# Connector.net
KiCad netlist of a schematic drawn in Altium Designer
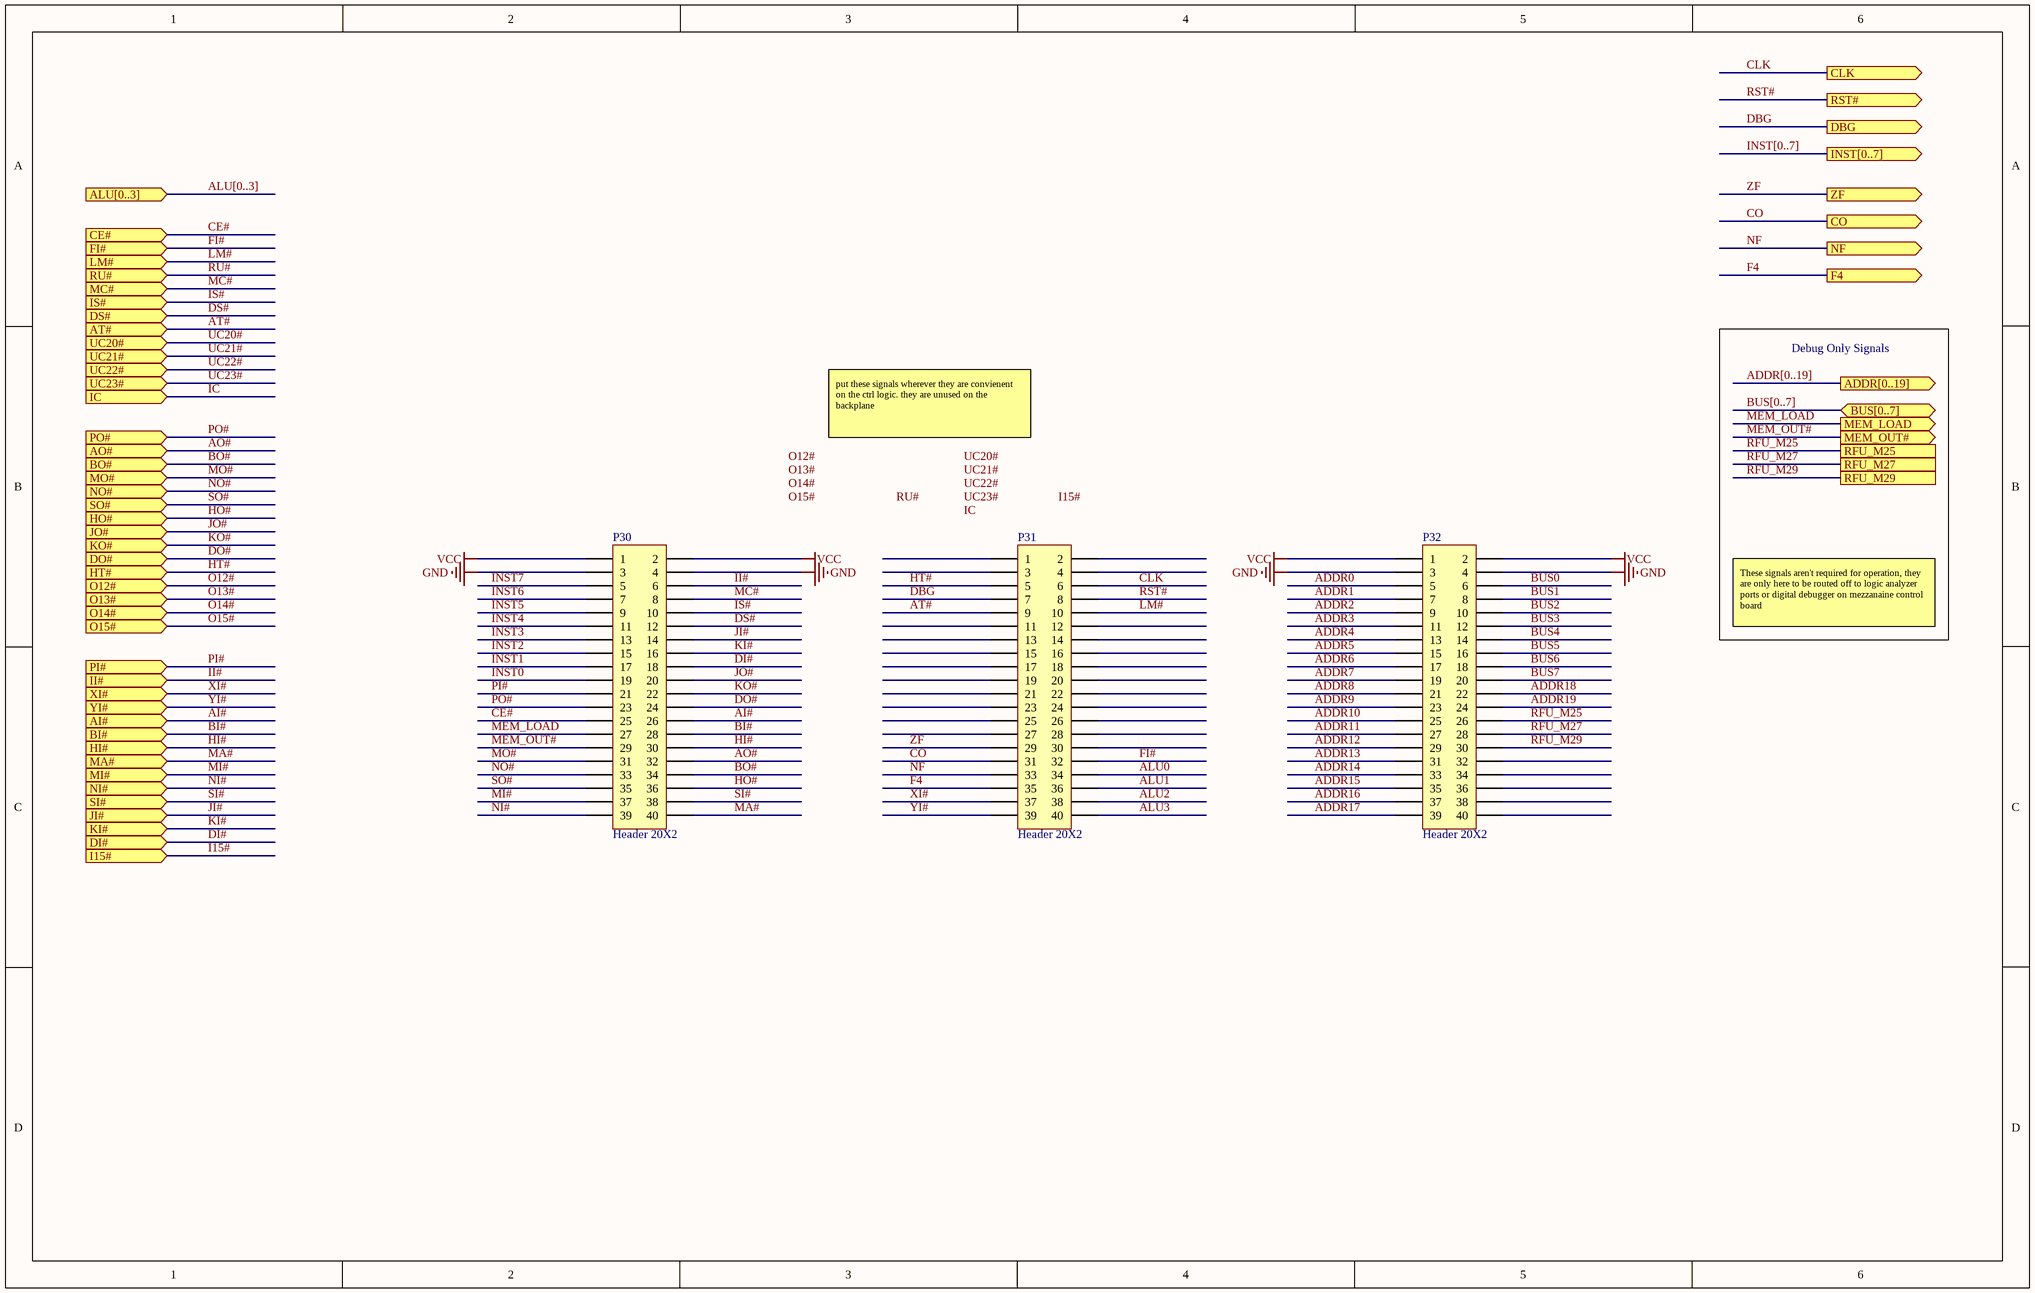
[diagram p0: Connector.SchDoc]

(export (version "E")
  (design (tool "Eeschema 10.0.6"))
  (components
    (comp (ref "P30")
      (value "Header 20X2")
      (footprint "HDR2X20")
      (description "Header, 20-Pin, Dual row")
      (fields (field (name "PUBLISHER") "Altium Limited"))
      (libsource (lib "Miscellaneous Connectors") (part "Header 20X2"))
    )
    (comp (ref "P31")
      (value "Header 20X2")
      (footprint "HDR2X20")
      (description "Header, 20-Pin, Dual row")
      (fields (field (name "PUBLISHER") "Altium Limited"))
      (libsource (lib "Miscellaneous Connectors") (part "Header 20X2"))
    )
    (comp (ref "P32")
      (value "Header 20X2")
      (footprint "HDR2X20")
      (description "Header, 20-Pin, Dual row")
      (fields (field (name "PUBLISHER") "Altium Limited"))
      (libsource (lib "Miscellaneous Connectors") (part "Header 20X2"))
    )
  )
  (nets
    (net (code "1") (name "/ADDR0") (class "Default")
      (node (ref "P32") (pin "5") (pinfunction "5_5") (pintype "passive"))
    )
    (net (code "2") (name "/ADDR1") (class "Default")
      (node (ref "P32") (pin "7") (pinfunction "7_7") (pintype "passive"))
    )
    (net (code "3") (name "/ADDR2") (class "Default")
      (node (ref "P32") (pin "9") (pinfunction "9_9") (pintype "passive"))
    )
    (net (code "4") (name "/ADDR3") (class "Default")
      (node (ref "P32") (pin "11") (pinfunction "11_11") (pintype "passive"))
    )
    (net (code "5") (name "/ADDR4") (class "Default")
      (node (ref "P32") (pin "13") (pinfunction "13_13") (pintype "passive"))
    )
    (net (code "6") (name "/ADDR5") (class "Default")
      (node (ref "P32") (pin "15") (pinfunction "15_15") (pintype "passive"))
    )
    (net (code "7") (name "/ADDR6") (class "Default")
      (node (ref "P32") (pin "17") (pinfunction "17_17") (pintype "passive"))
    )
    (net (code "8") (name "/ADDR7") (class "Default")
      (node (ref "P32") (pin "19") (pinfunction "19_19") (pintype "passive"))
    )
    (net (code "9") (name "/ADDR8") (class "Default")
      (node (ref "P32") (pin "21") (pinfunction "21_21") (pintype "passive"))
    )
    (net (code "10") (name "/ADDR9") (class "Default")
      (node (ref "P32") (pin "23") (pinfunction "23_23") (pintype "passive"))
    )
    (net (code "11") (name "/ADDR10") (class "Default")
      (node (ref "P32") (pin "25") (pinfunction "25_25") (pintype "passive"))
    )
    (net (code "12") (name "/ADDR11") (class "Default")
      (node (ref "P32") (pin "27") (pinfunction "27_27") (pintype "passive"))
    )
    (net (code "13") (name "/ADDR12") (class "Default")
      (node (ref "P32") (pin "29") (pinfunction "29_29") (pintype "passive"))
    )
    (net (code "14") (name "/ADDR13") (class "Default")
      (node (ref "P32") (pin "31") (pinfunction "31_31") (pintype "passive"))
    )
    (net (code "15") (name "/ADDR14") (class "Default")
      (node (ref "P32") (pin "33") (pinfunction "33_33") (pintype "passive"))
    )
    (net (code "16") (name "/ADDR15") (class "Default")
      (node (ref "P32") (pin "35") (pinfunction "35_35") (pintype "passive"))
    )
    (net (code "17") (name "/ADDR16") (class "Default")
      (node (ref "P32") (pin "37") (pinfunction "37_37") (pintype "passive"))
    )
    (net (code "18") (name "/ADDR17") (class "Default")
      (node (ref "P32") (pin "39") (pinfunction "39_39") (pintype "passive"))
    )
    (net (code "19") (name "/ADDR18") (class "Default")
      (node (ref "P32") (pin "22") (pinfunction "22_22") (pintype "passive"))
    )
    (net (code "20") (name "/ADDR19") (class "Default")
      (node (ref "P32") (pin "24") (pinfunction "24_24") (pintype "passive"))
    )
    (net (code "22") (name "/AI#") (class "Default")
      (node (ref "P30") (pin "26") (pinfunction "26_26") (pintype "passive"))
    )
    (net (code "23") (name "/ALU0") (class "Default")
      (node (ref "P31") (pin "34") (pinfunction "34_34") (pintype "passive"))
    )
    (net (code "24") (name "/ALU1") (class "Default")
      (node (ref "P31") (pin "36") (pinfunction "36_36") (pintype "passive"))
    )
    (net (code "25") (name "/ALU2") (class "Default")
      (node (ref "P31") (pin "38") (pinfunction "38_38") (pintype "passive"))
    )
    (net (code "26") (name "/ALU3") (class "Default")
      (node (ref "P31") (pin "40") (pinfunction "40_40") (pintype "passive"))
    )
    (net (code "28") (name "/AO#") (class "Default")
      (node (ref "P30") (pin "32") (pinfunction "32_32") (pintype "passive"))
    )
    (net (code "29") (name "/AT#") (class "Default")
      (node (ref "P31") (pin "9") (pinfunction "9_9") (pintype "passive"))
    )
    (net (code "30") (name "/BI#") (class "Default")
      (node (ref "P30") (pin "28") (pinfunction "28_28") (pintype "passive"))
    )
    (net (code "31") (name "/BO#") (class "Default")
      (node (ref "P30") (pin "34") (pinfunction "34_34") (pintype "passive"))
    )
    (net (code "32") (name "/BUS0") (class "Default")
      (node (ref "P32") (pin "6") (pinfunction "6_6") (pintype "passive"))
    )
    (net (code "33") (name "/BUS1") (class "Default")
      (node (ref "P32") (pin "8") (pinfunction "8_8") (pintype "passive"))
    )
    (net (code "34") (name "/BUS2") (class "Default")
      (node (ref "P32") (pin "10") (pinfunction "10_10") (pintype "passive"))
    )
    (net (code "35") (name "/BUS3") (class "Default")
      (node (ref "P32") (pin "12") (pinfunction "12_12") (pintype "passive"))
    )
    (net (code "36") (name "/BUS4") (class "Default")
      (node (ref "P32") (pin "14") (pinfunction "14_14") (pintype "passive"))
    )
    (net (code "37") (name "/BUS5") (class "Default")
      (node (ref "P32") (pin "16") (pinfunction "16_16") (pintype "passive"))
    )
    (net (code "38") (name "/BUS6") (class "Default")
      (node (ref "P32") (pin "18") (pinfunction "18_18") (pintype "passive"))
    )
    (net (code "39") (name "/BUS7") (class "Default")
      (node (ref "P32") (pin "20") (pinfunction "20_20") (pintype "passive"))
    )
    (net (code "41") (name "/CE#") (class "Default")
      (node (ref "P30") (pin "25") (pinfunction "25_25") (pintype "passive"))
    )
    (net (code "42") (name "/CLK") (class "Default")
      (node (ref "P31") (pin "6") (pinfunction "6_6") (pintype "passive"))
    )
    (net (code "43") (name "/CO") (class "Default")
      (node (ref "P31") (pin "31") (pinfunction "31_31") (pintype "passive"))
    )
    (net (code "44") (name "/DBG") (class "Default")
      (node (ref "P31") (pin "7") (pinfunction "7_7") (pintype "passive"))
    )
    (net (code "45") (name "/DI#") (class "Default")
      (node (ref "P30") (pin "18") (pinfunction "18_18") (pintype "passive"))
    )
    (net (code "46") (name "/DO#") (class "Default")
      (node (ref "P30") (pin "24") (pinfunction "24_24") (pintype "passive"))
    )
    (net (code "47") (name "/DS#") (class "Default")
      (node (ref "P30") (pin "12") (pinfunction "12_12") (pintype "passive"))
    )
    (net (code "48") (name "/F4") (class "Default")
      (node (ref "P31") (pin "35") (pinfunction "35_35") (pintype "passive"))
    )
    (net (code "49") (name "/FI#") (class "Default")
      (node (ref "P31") (pin "32") (pinfunction "32_32") (pintype "passive"))
    )
    (net (code "50") (name "/HI#") (class "Default")
      (node (ref "P30") (pin "30") (pinfunction "30_30") (pintype "passive"))
    )
    (net (code "51") (name "/HO#") (class "Default")
      (node (ref "P30") (pin "36") (pinfunction "36_36") (pintype "passive"))
    )
    (net (code "52") (name "/HT#") (class "Default")
      (node (ref "P31") (pin "5") (pinfunction "5_5") (pintype "passive"))
    )
    (net (code "55") (name "/II#") (class "Default")
      (node (ref "P30") (pin "6") (pinfunction "6_6") (pintype "passive"))
    )
    (net (code "56") (name "/INST0") (class "Default")
      (node (ref "P30") (pin "19") (pinfunction "19_19") (pintype "passive"))
    )
    (net (code "57") (name "/INST1") (class "Default")
      (node (ref "P30") (pin "17") (pinfunction "17_17") (pintype "passive"))
    )
    (net (code "58") (name "/INST2") (class "Default")
      (node (ref "P30") (pin "15") (pinfunction "15_15") (pintype "passive"))
    )
    (net (code "59") (name "/INST3") (class "Default")
      (node (ref "P30") (pin "13") (pinfunction "13_13") (pintype "passive"))
    )
    (net (code "60") (name "/INST4") (class "Default")
      (node (ref "P30") (pin "11") (pinfunction "11_11") (pintype "passive"))
    )
    (net (code "61") (name "/INST5") (class "Default")
      (node (ref "P30") (pin "9") (pinfunction "9_9") (pintype "passive"))
    )
    (net (code "62") (name "/INST6") (class "Default")
      (node (ref "P30") (pin "7") (pinfunction "7_7") (pintype "passive"))
    )
    (net (code "63") (name "/INST7") (class "Default")
      (node (ref "P30") (pin "5") (pinfunction "5_5") (pintype "passive"))
    )
    (net (code "65") (name "/IS#") (class "Default")
      (node (ref "P30") (pin "10") (pinfunction "10_10") (pintype "passive"))
    )
    (net (code "66") (name "/JI#") (class "Default")
      (node (ref "P30") (pin "14") (pinfunction "14_14") (pintype "passive"))
    )
    (net (code "67") (name "/JO#") (class "Default")
      (node (ref "P30") (pin "20") (pinfunction "20_20") (pintype "passive"))
    )
    (net (code "68") (name "/KI#") (class "Default")
      (node (ref "P30") (pin "16") (pinfunction "16_16") (pintype "passive"))
    )
    (net (code "69") (name "/KO#") (class "Default")
      (node (ref "P30") (pin "22") (pinfunction "22_22") (pintype "passive"))
    )
    (net (code "70") (name "/LM#") (class "Default")
      (node (ref "P31") (pin "10") (pinfunction "10_10") (pintype "passive"))
    )
    (net (code "71") (name "/MA#") (class "Default")
      (node (ref "P30") (pin "40") (pinfunction "40_40") (pintype "passive"))
    )
    (net (code "72") (name "/MC#") (class "Default")
      (node (ref "P30") (pin "8") (pinfunction "8_8") (pintype "passive"))
    )
    (net (code "73") (name "/MEM_LOAD") (class "Default")
      (node (ref "P30") (pin "27") (pinfunction "27_27") (pintype "passive"))
    )
    (net (code "74") (name "/MEM_OUT#") (class "Default")
      (node (ref "P30") (pin "29") (pinfunction "29_29") (pintype "passive"))
    )
    (net (code "75") (name "/MI#") (class "Default")
      (node (ref "P30") (pin "37") (pinfunction "37_37") (pintype "passive"))
    )
    (net (code "76") (name "/MO#") (class "Default")
      (node (ref "P30") (pin "31") (pinfunction "31_31") (pintype "passive"))
    )
    (net (code "77") (name "/NF") (class "Default")
      (node (ref "P31") (pin "33") (pinfunction "33_33") (pintype "passive"))
    )
    (net (code "78") (name "/NI#") (class "Default")
      (node (ref "P30") (pin "39") (pinfunction "39_39") (pintype "passive"))
    )
    (net (code "79") (name "/NO#") (class "Default")
      (node (ref "P30") (pin "33") (pinfunction "33_33") (pintype "passive"))
    )
    (net (code "84") (name "/PI#") (class "Default")
      (node (ref "P30") (pin "21") (pinfunction "21_21") (pintype "passive"))
    )
    (net (code "85") (name "/PO#") (class "Default")
      (node (ref "P30") (pin "23") (pinfunction "23_23") (pintype "passive"))
    )
    (net (code "86") (name "/RFU_M25") (class "Default")
      (node (ref "P32") (pin "26") (pinfunction "26_26") (pintype "passive"))
    )
    (net (code "87") (name "/RFU_M27") (class "Default")
      (node (ref "P32") (pin "28") (pinfunction "28_28") (pintype "passive"))
    )
    (net (code "88") (name "/RFU_M29") (class "Default")
      (node (ref "P32") (pin "30") (pinfunction "30_30") (pintype "passive"))
    )
    (net (code "89") (name "/RST#") (class "Default")
      (node (ref "P31") (pin "8") (pinfunction "8_8") (pintype "passive"))
    )
    (net (code "91") (name "/SI#") (class "Default")
      (node (ref "P30") (pin "38") (pinfunction "38_38") (pintype "passive"))
    )
    (net (code "92") (name "/SO#") (class "Default")
      (node (ref "P30") (pin "35") (pinfunction "35_35") (pintype "passive"))
    )
    (net (code "97") (name "/XI#") (class "Default")
      (node (ref "P31") (pin "37") (pinfunction "37_37") (pintype "passive"))
    )
    (net (code "98") (name "/YI#") (class "Default")
      (node (ref "P31") (pin "39") (pinfunction "39_39") (pintype "passive"))
    )
    (net (code "99") (name "/ZF") (class "Default")
      (node (ref "P31") (pin "29") (pinfunction "29_29") (pintype "passive"))
    )
    (net (code "100") (name "GND") (class "Default")
      (node (ref "P30") (pin "3") (pinfunction "3_3") (pintype "passive"))
      (node (ref "P30") (pin "4") (pinfunction "4_4") (pintype "passive"))
      (node (ref "P32") (pin "3") (pinfunction "3_3") (pintype "passive"))
      (node (ref "P32") (pin "4") (pinfunction "4_4") (pintype "passive"))
    )
    (net (code "101") (name "VCC") (class "Default")
      (node (ref "P30") (pin "1") (pinfunction "1_1") (pintype "passive"))
      (node (ref "P30") (pin "2") (pinfunction "2_2") (pintype "passive"))
      (node (ref "P32") (pin "1") (pinfunction "1_1") (pintype "passive"))
      (node (ref "P32") (pin "2") (pinfunction "2_2") (pintype "passive"))
    )
    (net (code "102") (name "unconnected-(P31-Pad1)") (class "Default")
      (node (ref "P31") (pin "1") (pinfunction "1_1") (pintype "passive"))
    )
    (net (code "103") (name "unconnected-(P31-Pad2)") (class "Default")
      (node (ref "P31") (pin "2") (pinfunction "2_2") (pintype "passive"))
    )
    (net (code "104") (name "unconnected-(P31-Pad3)") (class "Default")
      (node (ref "P31") (pin "3") (pinfunction "3_3") (pintype "passive"))
    )
    (net (code "105") (name "unconnected-(P31-Pad4)") (class "Default")
      (node (ref "P31") (pin "4") (pinfunction "4_4") (pintype "passive"))
    )
    (net (code "106") (name "unconnected-(P31-Pad11)") (class "Default")
      (node (ref "P31") (pin "11") (pinfunction "11_11") (pintype "passive"))
    )
    (net (code "107") (name "unconnected-(P31-Pad12)") (class "Default")
      (node (ref "P31") (pin "12") (pinfunction "12_12") (pintype "passive"))
    )
    (net (code "108") (name "unconnected-(P31-Pad13)") (class "Default")
      (node (ref "P31") (pin "13") (pinfunction "13_13") (pintype "passive"))
    )
    (net (code "109") (name "unconnected-(P31-Pad14)") (class "Default")
      (node (ref "P31") (pin "14") (pinfunction "14_14") (pintype "passive"))
    )
    (net (code "110") (name "unconnected-(P31-Pad15)") (class "Default")
      (node (ref "P31") (pin "15") (pinfunction "15_15") (pintype "passive"))
    )
    (net (code "111") (name "unconnected-(P31-Pad16)") (class "Default")
      (node (ref "P31") (pin "16") (pinfunction "16_16") (pintype "passive"))
    )
    (net (code "112") (name "unconnected-(P31-Pad17)") (class "Default")
      (node (ref "P31") (pin "17") (pinfunction "17_17") (pintype "passive"))
    )
    (net (code "113") (name "unconnected-(P31-Pad18)") (class "Default")
      (node (ref "P31") (pin "18") (pinfunction "18_18") (pintype "passive"))
    )
    (net (code "114") (name "unconnected-(P31-Pad19)") (class "Default")
      (node (ref "P31") (pin "19") (pinfunction "19_19") (pintype "passive"))
    )
    (net (code "115") (name "unconnected-(P31-Pad20)") (class "Default")
      (node (ref "P31") (pin "20") (pinfunction "20_20") (pintype "passive"))
    )
    (net (code "116") (name "unconnected-(P31-Pad21)") (class "Default")
      (node (ref "P31") (pin "21") (pinfunction "21_21") (pintype "passive"))
    )
    (net (code "117") (name "unconnected-(P31-Pad22)") (class "Default")
      (node (ref "P31") (pin "22") (pinfunction "22_22") (pintype "passive"))
    )
    (net (code "118") (name "unconnected-(P31-Pad23)") (class "Default")
      (node (ref "P31") (pin "23") (pinfunction "23_23") (pintype "passive"))
    )
    (net (code "119") (name "unconnected-(P31-Pad24)") (class "Default")
      (node (ref "P31") (pin "24") (pinfunction "24_24") (pintype "passive"))
    )
    (net (code "120") (name "unconnected-(P31-Pad25)") (class "Default")
      (node (ref "P31") (pin "25") (pinfunction "25_25") (pintype "passive"))
    )
    (net (code "121") (name "unconnected-(P31-Pad26)") (class "Default")
      (node (ref "P31") (pin "26") (pinfunction "26_26") (pintype "passive"))
    )
    (net (code "122") (name "unconnected-(P31-Pad27)") (class "Default")
      (node (ref "P31") (pin "27") (pinfunction "27_27") (pintype "passive"))
    )
    (net (code "123") (name "unconnected-(P31-Pad28)") (class "Default")
      (node (ref "P31") (pin "28") (pinfunction "28_28") (pintype "passive"))
    )
    (net (code "124") (name "unconnected-(P31-Pad30)") (class "Default")
      (node (ref "P31") (pin "30") (pinfunction "30_30") (pintype "passive"))
    )
    (net (code "125") (name "unconnected-(P32-Pad32)") (class "Default")
      (node (ref "P32") (pin "32") (pinfunction "32_32") (pintype "passive"))
    )
    (net (code "126") (name "unconnected-(P32-Pad34)") (class "Default")
      (node (ref "P32") (pin "34") (pinfunction "34_34") (pintype "passive"))
    )
    (net (code "127") (name "unconnected-(P32-Pad36)") (class "Default")
      (node (ref "P32") (pin "36") (pinfunction "36_36") (pintype "passive"))
    )
    (net (code "128") (name "unconnected-(P32-Pad38)") (class "Default")
      (node (ref "P32") (pin "38") (pinfunction "38_38") (pintype "passive"))
    )
    (net (code "129") (name "unconnected-(P32-Pad40)") (class "Default")
      (node (ref "P32") (pin "40") (pinfunction "40_40") (pintype "passive"))
    )
  )
)
